# mqtt_doorbell_v1_1.net
KiCad netlist of a schematic drawn in EAGLE
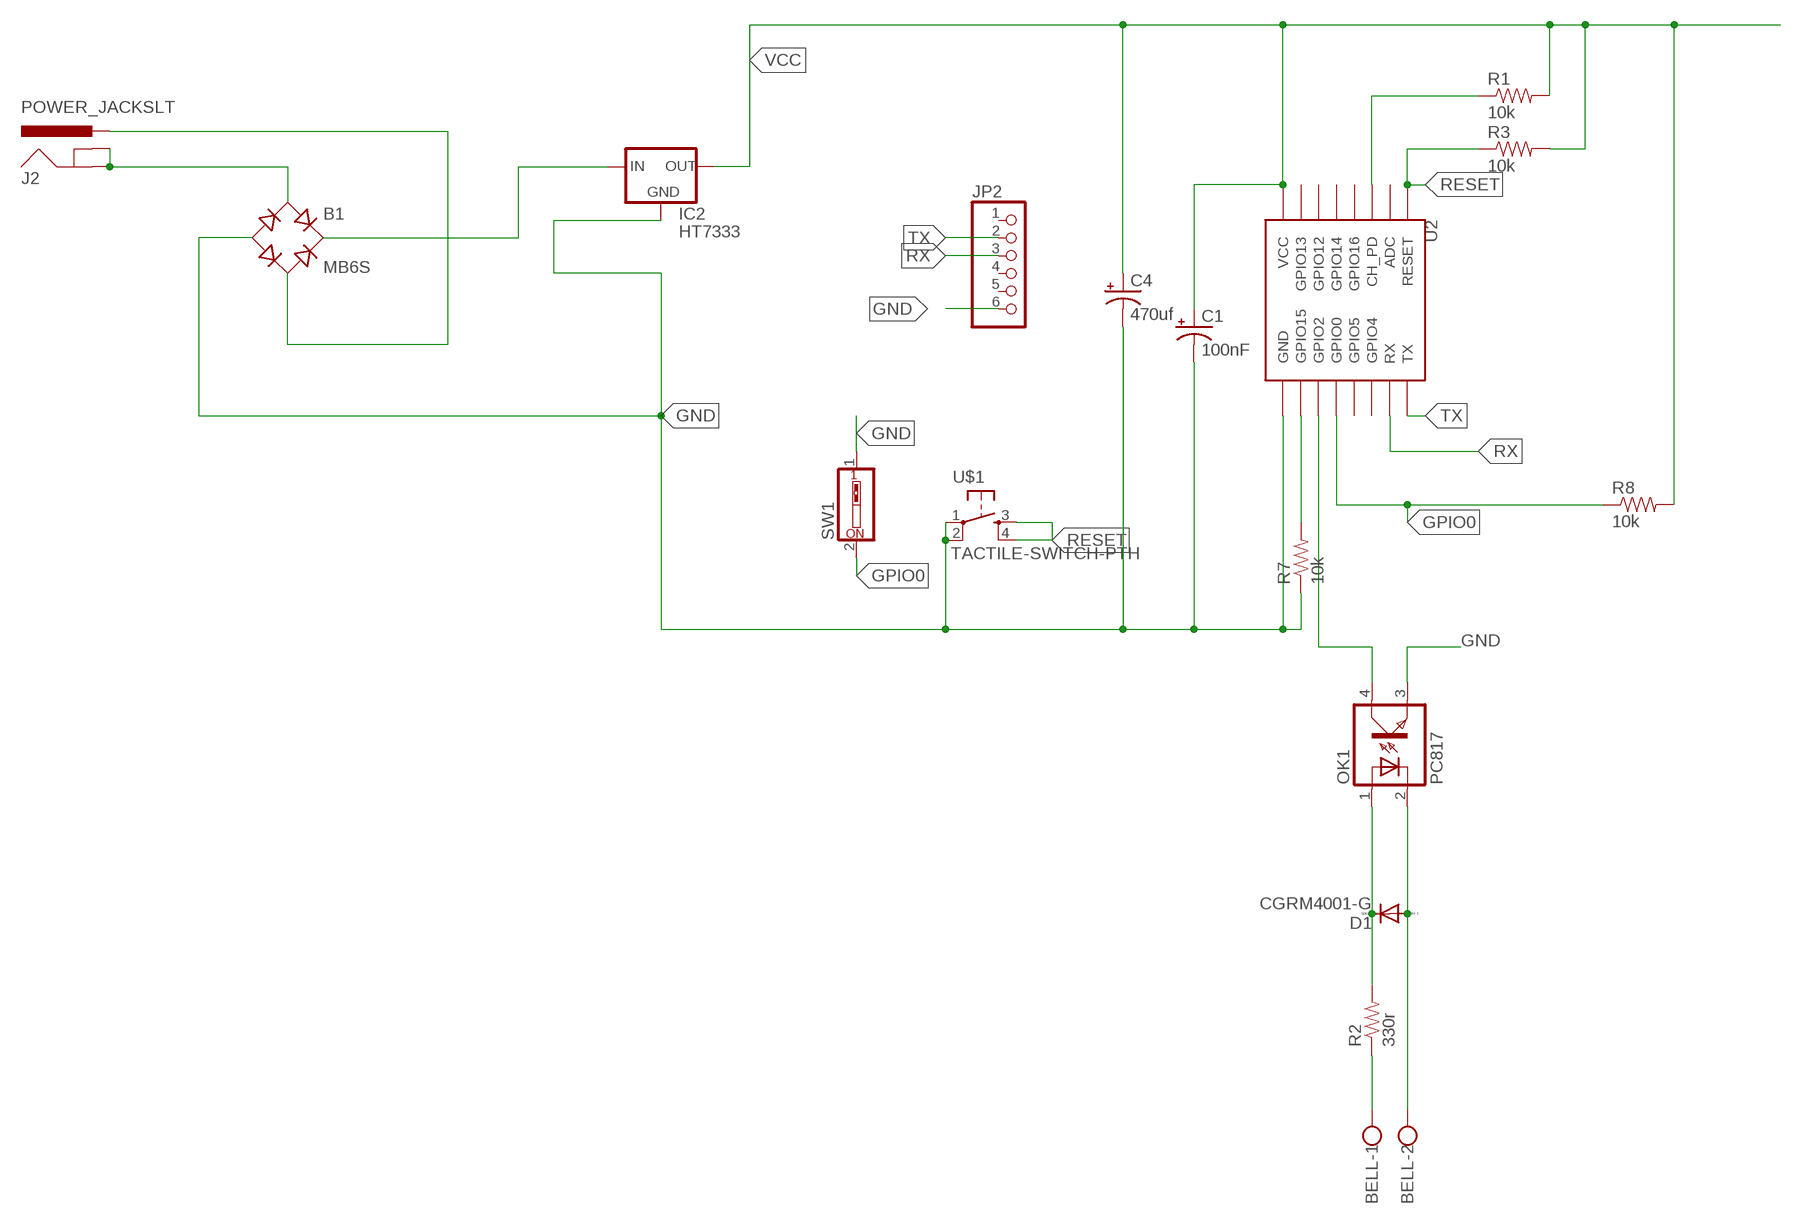
[diagram p0: schematic, sheet 1]

(export (version "E")
  (design (tool "Eeschema 10.0.6"))
  (components
    (comp (ref "B1")
      (value "MB6S")
      (footprint "eagle-import:SOIC-4")
      (libsource (lib "eagle-import") (part "MBS4"))
    )
    (comp (ref "BELL")
      (value "W237-102")
      (footprint "eagle-import:W237-102")
      (fields (field (name "MPN") "237-102"))
      (libsource (lib "eagle-import") (part "W237-102"))
    )
    (comp (ref "C1")
      (value "100nF")
      (footprint "eagle-import:EIA3216")
      (libsource (lib "eagle-import") (part "10UF-16V-10%(TANT)"))
    )
    (comp (ref "C4")
      (value "470uf")
      (footprint "eagle-import:PANASONIC_D")
      (libsource (lib "eagle-import") (part "47UF-50V-20%(ELECT)"))
    )
    (comp (ref "D1")
      (value "CGRM4001-G")
      (footprint "eagle-import:SOD-123_MINI-SMA")
      (libsource (lib "eagle-import") (part "CGRM400-G1"))
    )
    (comp (ref "IC2")
      (value "HT7333")
      (footprint "eagle-import:SOT-89")
      (libsource (lib "eagle-import") (part "HT7333"))
    )
    (comp (ref "J2")
      (value "POWER_JACKSLT")
      (footprint "eagle-import:POWER_JACK_SLOT")
      (libsource (lib "eagle-import") (part "POWER_JACKSLT"))
    )
    (comp (ref "JP2")
      (value "PINHD-1X6")
      (footprint "eagle-import:1X06")
      (libsource (lib "eagle-import") (part "PINHD-1X6"))
    )
    (comp (ref "OK1")
      (value "PC817")
      (footprint "eagle-import:DIL04")
      (fields (field (name "MPN") "PC817X4J000F"))
      (libsource (lib "eagle-import") (part "PC817"))
    )
    (comp (ref "R1")
      (value "10k")
      (footprint "eagle-import:1206")
      (libsource (lib "eagle-import") (part "RESISTOR1206"))
    )
    (comp (ref "R2")
      (value "330r")
      (footprint "eagle-import:1206")
      (libsource (lib "eagle-import") (part "RESISTOR1206"))
    )
    (comp (ref "R3")
      (value "10k")
      (footprint "eagle-import:1206")
      (libsource (lib "eagle-import") (part "RESISTOR1206"))
    )
    (comp (ref "R7")
      (value "10k")
      (footprint "eagle-import:1206")
      (libsource (lib "eagle-import") (part "RESISTOR1206"))
    )
    (comp (ref "R8")
      (value "10k")
      (footprint "eagle-import:1206")
      (libsource (lib "eagle-import") (part "RESISTOR1206"))
    )
    (comp (ref "SW1")
      (value "SW_DIP-1")
      (footprint "eagle-import:EDG-01")
      (libsource (lib "eagle-import") (part "SW_DIP-1"))
    )
    (comp (ref "U$1")
      (value "TACTILE-SWITCH-PTH")
      (footprint "eagle-import:TAC-SWITCH-PTH")
      (libsource (lib "eagle-import") (part "TACTILE-SWITCH-PTH"))
    )
    (comp (ref "U2")
      (value "ESP12SMD")
      (footprint "eagle-import:ESP12-SMD")
      (libsource (lib "eagle-import") (part "ESP12SMD"))
    )
  )
  (nets
    (net (code "1") (name "GND") (class "Default")
      (node (ref "B1") (pin "-") (pinfunction "-_-") (pintype "passive"))
      (node (ref "C1") (pin "C") (pinfunction "-_C") (pintype "passive"))
      (node (ref "C4") (pin "-") (pinfunction "-_-") (pintype "passive"))
      (node (ref "IC2") (pin "2") (pinfunction "GND_2") (pintype "input"))
      (node (ref "JP2") (pin "6") (pinfunction "6_6") (pintype "passive"))
      (node (ref "OK1") (pin "3") (pinfunction "EMIT_3") (pintype "passive"))
      (node (ref "R7") (pin "1") (pinfunction "1_1") (pintype "passive"))
      (node (ref "SW1") (pin "1") (pinfunction "1_1") (pintype "passive"))
      (node (ref "U$1") (pin "1") (pinfunction "1_1") (pintype "passive"))
      (node (ref "U$1") (pin "2") (pinfunction "2_2") (pintype "passive"))
      (node (ref "U2") (pin "GND") (pinfunction "GND_GND") (pintype "bidirectional"))
    )
    (net (code "2") (name "GPIO0") (class "Default")
      (node (ref "R8") (pin "1") (pinfunction "1_1") (pintype "passive"))
      (node (ref "SW1") (pin "2") (pinfunction "2_2") (pintype "passive"))
      (node (ref "U2") (pin "GPIO0") (pinfunction "GPIO0_GPIO0") (pintype "bidirectional"))
    )
    (net (code "3") (name "Net-(B1-AC1)") (class "Default")
      (node (ref "B1") (pin "~1") (pinfunction "AC1_~1") (pintype "passive"))
      (node (ref "J2") (pin "GND@1") (pinfunction "GNDBREAK_GND@1") (pintype "bidirectional"))
      (node (ref "J2") (pin "GND@2") (pinfunction "GND_GND@2") (pintype "bidirectional"))
    )
    (net (code "4") (name "Net-(B1-AC2)") (class "Default")
      (node (ref "B1") (pin "~2") (pinfunction "AC2_~2") (pintype "passive"))
      (node (ref "J2") (pin "PWR") (pinfunction "PWR_PWR") (pintype "bidirectional"))
    )
    (net (code "5") (name "Net-(B1-Pad+)") (class "Default")
      (node (ref "B1") (pin "+") (pinfunction "+_+") (pintype "passive"))
      (node (ref "IC2") (pin "3") (pinfunction "IN_3") (pintype "input"))
      (node (ref "IC2") (pin "4") (pinfunction "IN_4") (pintype "input"))
    )
    (net (code "6") (name "Net-(BELLA-KL)") (class "Default")
      (node (ref "BELL") (pin "1") (pinfunction "KL_1") (pintype "passive"))
      (node (ref "R2") (pin "1") (pinfunction "1_1") (pintype "passive"))
    )
    (net (code "7") (name "Net-(BELLB-KL)") (class "Default")
      (node (ref "BELL") (pin "2") (pinfunction "KL_2") (pintype "passive"))
      (node (ref "D1") (pin "A") (pinfunction "A_A") (pintype "passive"))
      (node (ref "OK1") (pin "2") (pinfunction "C_2") (pintype "passive"))
    )
    (net (code "8") (name "Net-(OK1-A)") (class "Default")
      (node (ref "D1") (pin "C") (pinfunction "C_C") (pintype "passive"))
      (node (ref "OK1") (pin "1") (pinfunction "A_1") (pintype "passive"))
      (node (ref "R2") (pin "2") (pinfunction "2_2") (pintype "passive"))
    )
    (net (code "9") (name "Net-(OK1-COL)") (class "Default")
      (node (ref "OK1") (pin "4") (pinfunction "COL_4") (pintype "passive"))
      (node (ref "U2") (pin "GPIO2") (pinfunction "GPIO2_GPIO2") (pintype "bidirectional"))
    )
    (net (code "10") (name "Net-(R1-Pad1)") (class "Default")
      (node (ref "R1") (pin "1") (pinfunction "1_1") (pintype "passive"))
      (node (ref "U2") (pin "CH_PD") (pinfunction "CH_PD_CH_PD") (pintype "bidirectional"))
    )
    (net (code "11") (name "Net-(R7-Pad2)") (class "Default")
      (node (ref "R7") (pin "2") (pinfunction "2_2") (pintype "passive"))
      (node (ref "U2") (pin "GPIO15") (pinfunction "GPIO15_GPIO15") (pintype "bidirectional"))
    )
    (net (code "12") (name "RESET") (class "Default")
      (node (ref "R3") (pin "1") (pinfunction "1_1") (pintype "passive"))
      (node (ref "U$1") (pin "3") (pinfunction "3_3") (pintype "passive"))
      (node (ref "U$1") (pin "4") (pinfunction "4_4") (pintype "passive"))
      (node (ref "U2") (pin "RESET") (pinfunction "RESET_RESET") (pintype "bidirectional"))
    )
    (net (code "13") (name "RX") (class "Default")
      (node (ref "JP2") (pin "3") (pinfunction "3_3") (pintype "passive"))
      (node (ref "U2") (pin "RXD0") (pinfunction "RX_RXD0") (pintype "bidirectional"))
    )
    (net (code "14") (name "TX") (class "Default")
      (node (ref "JP2") (pin "2") (pinfunction "2_2") (pintype "passive"))
      (node (ref "U2") (pin "TXD0") (pinfunction "TX_TXD0") (pintype "bidirectional"))
    )
    (net (code "15") (name "VCC") (class "Default")
      (node (ref "C1") (pin "A") (pinfunction "+_A") (pintype "passive"))
      (node (ref "C4") (pin "+") (pinfunction "+_+") (pintype "passive"))
      (node (ref "IC2") (pin "1") (pinfunction "OUT_1") (pintype "passive"))
      (node (ref "R1") (pin "2") (pinfunction "2_2") (pintype "passive"))
      (node (ref "R3") (pin "2") (pinfunction "2_2") (pintype "passive"))
      (node (ref "R8") (pin "2") (pinfunction "2_2") (pintype "passive"))
      (node (ref "U2") (pin "VCC") (pinfunction "VCC_VCC") (pintype "bidirectional"))
    )
    (net (code "16") (name "unconnected-(JP2-Pad1)") (class "Default")
      (node (ref "JP2") (pin "1") (pinfunction "1_1") (pintype "passive"))
    )
    (net (code "17") (name "unconnected-(JP2-Pad4)") (class "Default")
      (node (ref "JP2") (pin "4") (pinfunction "4_4") (pintype "passive"))
    )
    (net (code "18") (name "unconnected-(JP2-Pad5)") (class "Default")
      (node (ref "JP2") (pin "5") (pinfunction "5_5") (pintype "passive"))
    )
    (net (code "19") (name "unconnected-(U2-PadADC)") (class "Default")
      (node (ref "U2") (pin "ADC") (pinfunction "ADC_ADC") (pintype "bidirectional"))
    )
    (net (code "20") (name "unconnected-(U2-PadGPIO4)") (class "Default")
      (node (ref "U2") (pin "GPIO4") (pinfunction "GPIO4_GPIO4") (pintype "bidirectional"))
    )
    (net (code "21") (name "unconnected-(U2-PadGPIO5)") (class "Default")
      (node (ref "U2") (pin "GPIO5") (pinfunction "GPIO5_GPIO5") (pintype "bidirectional"))
    )
    (net (code "22") (name "unconnected-(U2-PadGPIO12)") (class "Default")
      (node (ref "U2") (pin "GPIO12") (pinfunction "GPIO12_GPIO12") (pintype "bidirectional"))
    )
    (net (code "23") (name "unconnected-(U2-PadGPIO13)") (class "Default")
      (node (ref "U2") (pin "GPIO13") (pinfunction "GPIO13_GPIO13") (pintype "bidirectional"))
    )
    (net (code "24") (name "unconnected-(U2-PadGPIO14)") (class "Default")
      (node (ref "U2") (pin "GPIO14") (pinfunction "GPIO14_GPIO14") (pintype "bidirectional"))
    )
    (net (code "25") (name "unconnected-(U2-PadGPIO16)") (class "Default")
      (node (ref "U2") (pin "GPIO16") (pinfunction "GPIO16_GPIO16") (pintype "bidirectional"))
    )
  )
)
